# main.net
KiCad netlist of a schematic drawn in Altium Designer
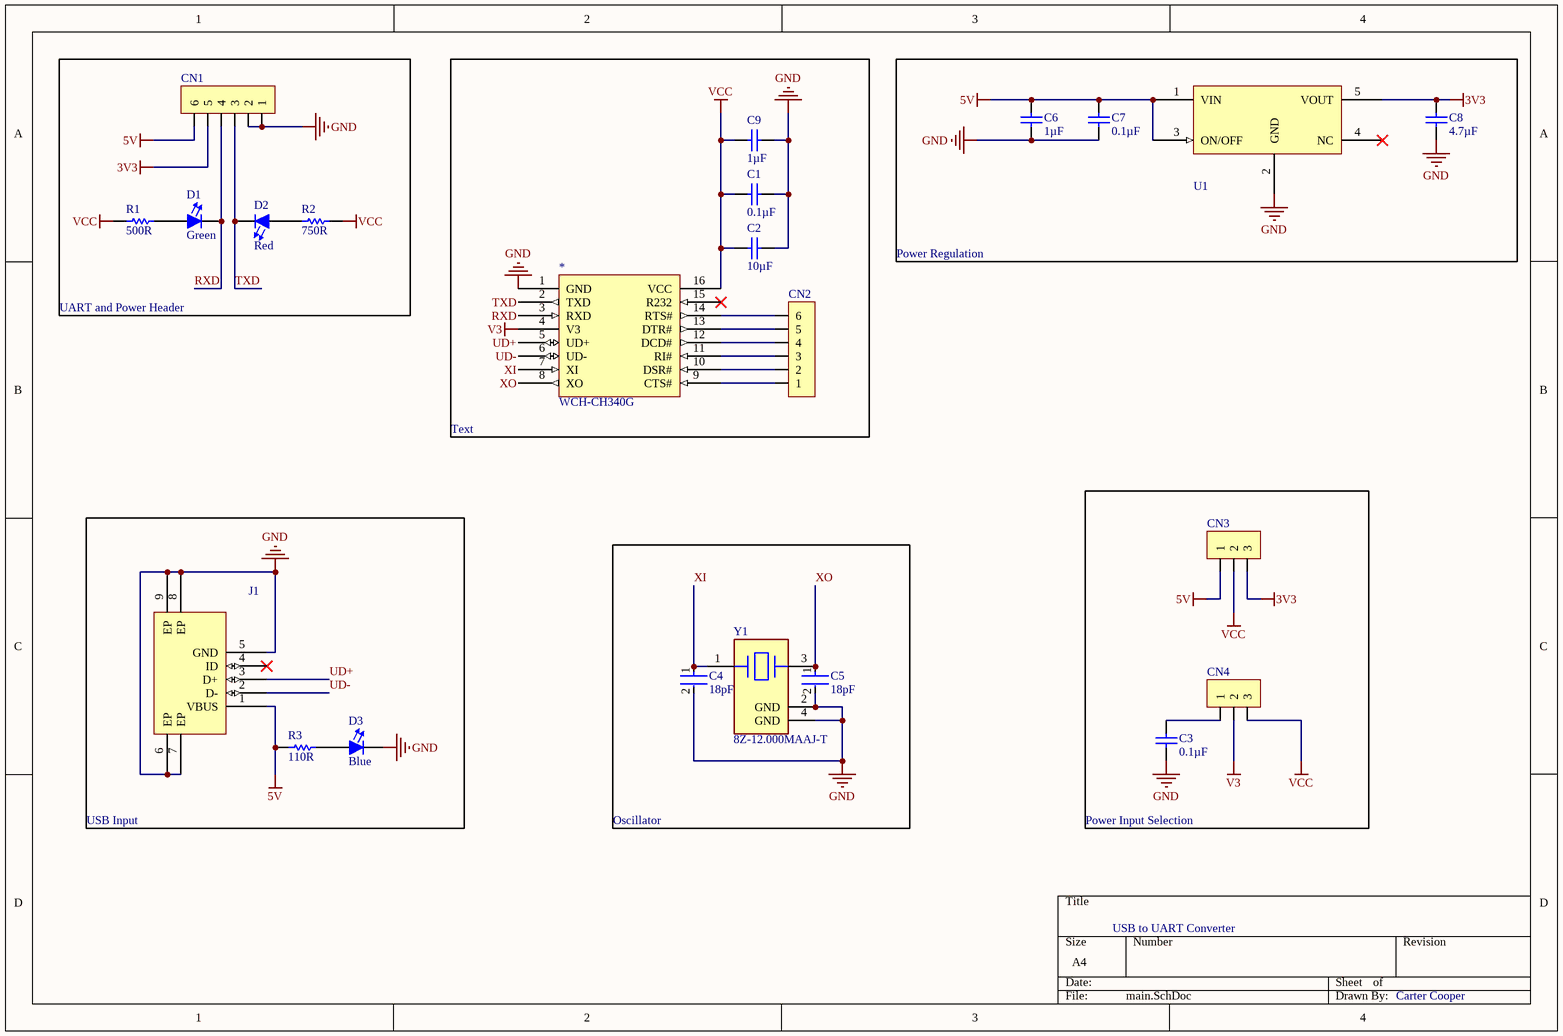
[diagram p0: main.SchDoc]

(export (version "E")
  (design (tool "Eeschema 10.0.6"))
  (components
    (comp (ref "*")
      (value "WCH-CH340G")
      (footprint "SOP127P600X175-16N")
      (description "USB to UART Transceiver. USB 2.0 2Mbps. LCSC #C14267")
      (fields (field (name "LCSC PART NUMBER") "C14267"))
      (libsource (lib "AUVIC") (part "WCH-CH340G"))
    )
    (comp (ref "C1")
      (value "0.1µF")
      (footprint "CAPC1608N(0603\")")
      (description "Capacitor, Ceramic, 16V, +/- 10%, 0603 SMD, X7R")
      (fields
        (field (name "Comment") "0.1uF 16V 0603 SMD, Ceramic")
        (field (name "CREATED BY") "Andy Bates")
        (field (name "SOURCE") "AUVic_Schematic_Library_Capacitors.SchLib")
        (field (name "PUBLISHER") "AUVic")
      )
      (libsource (lib "AUVIC") (part "Symbol"))
    )
    (comp (ref "C2")
      (value "10µF")
      (footprint "CAPC1608N(0603\")")
      (description "Capacitor, Ceramic, 16V, +/- 10%, 0603 SMD, X7R")
      (fields
        (field (name "Comment") "0.1uF 16V 0603 SMD, Ceramic")
        (field (name "CREATED BY") "Andy Bates")
        (field (name "SOURCE") "AUVic_Schematic_Library_Capacitors.SchLib")
        (field (name "PUBLISHER") "AUVic")
      )
      (libsource (lib "AUVIC") (part "Symbol"))
    )
    (comp (ref "C3")
      (value "0.1µF")
      (footprint "CAPC1608N(0603\")")
      (description "Capacitor, Ceramic, 16V, +/- 10%, 0603 SMD, X7R")
      (fields
        (field (name "Comment") "0.1uF 16V 0603 SMD, Ceramic")
        (field (name "CREATED BY") "Andy Bates")
        (field (name "SOURCE") "AUVic_Schematic_Library_Capacitors.SchLib")
        (field (name "PUBLISHER") "AUVic")
      )
      (libsource (lib "AUVIC") (part "Symbol"))
    )
    (comp (ref "C4")
      (value "CGA3E2C0G1H180J080AA")
      (footprint "FP-CGA3E-0_3-0_1-MFG")
      (description "CAP CER 18PF 50V C0G 0603")
      (fields (field (name "CAPACITANCE") "18pF") (field (name "TOLERANCE") "5%"))
      (libsource (lib "AUVIC") (part "b4654b650e69147ec39a6b967a45e02"))
    )
    (comp (ref "C5")
      (value "CGA3E2C0G1H180J080AA")
      (footprint "FP-CGA3E-0_3-0_1-MFG")
      (description "CAP CER 18PF 50V C0G 0603")
      (fields (field (name "CAPACITANCE") "18pF") (field (name "TOLERANCE") "5%"))
      (libsource (lib "AUVIC") (part "b4654b650e69147ec39a6b967a45e02"))
    )
    (comp (ref "C6")
      (value "1µF")
      (footprint "CAPC1608N(0603\")")
      (description "Capacitor, Ceramic, 50V, +/- 10%, 0603 SMD, X5R")
      (fields
        (field (name "Comment") "1uF 50V 0603 SMD, Ceramic")
        (field (name "CREATED BY") "Lyden Smith")
        (field (name "SOURCE") "AUVic_Schematic_Library_Capacitors.SchLib")
      )
      (libsource (lib "AUVIC") (part "Symbol"))
    )
    (comp (ref "C7")
      (value "0.1µF")
      (footprint "CAPC1608N(0603\")")
      (description "Capacitor, Ceramic, 16V, +/- 10%, 0603 SMD, X7R")
      (fields
        (field (name "Comment") "0.1uF 16V 0603 SMD, Ceramic")
        (field (name "CREATED BY") "Andy Bates")
        (field (name "SOURCE") "AUVic_Schematic_Library_Capacitors.SchLib")
        (field (name "PUBLISHER") "AUVic")
      )
      (libsource (lib "AUVIC") (part "Symbol"))
    )
    (comp (ref "C8")
      (value "4.7µF")
      (footprint "CAPC1608N(0603\")")
      (description "Capacitor, Ceramic, 10V, +/- 10%, 0603 SMD, X5R")
      (fields
        (field (name "MFG") "Samsung")
        (field (name "Comment") "4.7uF 10V 0603 SMD, Ceramic")
        (field (name "SOURCE") "AUVic_Schematic_Library_Capacitors.SchLib")
        (field (name "CREATED BY") "Ashwin Sira")
        (field (name "PUBLISHER") "AUVic")
      )
      (libsource (lib "AUVIC") (part "Symbol"))
    )
    (comp (ref "C9")
      (value "1µF")
      (footprint "CAPC1608N(0603\")")
      (description "Capacitor, Ceramic, 50V, +/- 10%, 0603 SMD, X5R")
      (fields
        (field (name "Comment") "1uF 50V 0603 SMD, Ceramic")
        (field (name "CREATED BY") "Lyden Smith")
        (field (name "SOURCE") "AUVic_Schematic_Library_Capacitors.SchLib")
      )
      (libsource (lib "AUVIC") (part "Symbol"))
    )
    (comp (ref "CN1")
      (value "Header, Male, 1x6")
      (footprint "Header, Male, 1X6")
      (description "1x6, Pads Pitch: 0.1\" (2.54mm), Through hole")
      (fields (field (name "SOURCE") "AUVic_Schematic_Library_Connectors.SchLib"))
      (libsource (lib "") (part "Symbol_4"))
    )
    (comp (ref "CN2")
      (value "Header, Male, 1x6")
      (footprint "Header, Male, 1X6")
      (description "1x6, Pads Pitch: 0.1\" (2.54mm), Through hole")
      (fields (field (name "SOURCE") "AUVic_Schematic_Library_Connectors.SchLib"))
      (libsource (lib "") (part "Symbol_1"))
    )
    (comp (ref "CN3")
      (value "Header, Male, 1x3, Pitch: 0.1\" (2.54mm), THT")
      (footprint "Header, Male, 1x3, Pitch: 0.1\" (2.54mm),THT")
      (fields
        (field (name "CREATED BY") "Ashwin Sira")
        (field (name "REVIEWED BY") "*")
        (field (name "SOURCE") "AUVic_Schematic_Library_Connectors.SchLib")
        (field (name "PUBLISHER") "AUVic")
      )
      (libsource (lib "") (part "Symbol_3"))
    )
    (comp (ref "CN4")
      (value "Header, Male, 1x3, Pitch: 0.1\" (2.54mm), THT")
      (footprint "Header, Male, 1x3, Pitch: 0.1\" (2.54mm),THT")
      (fields
        (field (name "CREATED BY") "Ashwin Sira")
        (field (name "REVIEWED BY") "*")
        (field (name "SOURCE") "AUVic_Schematic_Library_Connectors.SchLib")
        (field (name "PUBLISHER") "AUVic")
      )
      (libsource (lib "") (part "Symbol_3"))
    )
    (comp (ref "D1")
      (value "LT Q39G-Q1OO-25-1")
      (footprint "FP-LB_Q39E-MFG")
      (description "LED GREEN DIFFUSED 0603 SMD")
      (fields (field (name "COLOR") "Green"))
      (libsource (lib "") (part "Symbol_2"))
    )
    (comp (ref "D2")
      (value "LSQ976-NR-1")
      (footprint "FP-LB_Q39E-MFG")
      (description "LED Red 645nm 2-Pin Chip 0603(1608Metric) T/R")
      (fields (field (name "COLOR") "Red"))
      (libsource (lib "") (part "Symbol_2"))
    )
    (comp (ref "D3")
      (value "LBQ39E-N1OO-35-1")
      (footprint "FP-LB_Q39E-MFG")
      (description "LED BLUE DIFFUSED 0603 SMD")
      (fields (field (name "COLOR") "Blue"))
      (libsource (lib "") (part "Symbol_2"))
    )
    (comp (ref "J1")
      (value "USB - Micro B Female SMD")
      (footprint "Edge Connector")
      (description "USB - Micro B Female USB 2 5 SMD USB Connectors")
      (fields (field (name "LCSC PART NUMBER") "C319170") (field (name "CREATED BY") "Miguel Manguerra"))
      (libsource (lib "AUVIC") (part "USB - Micro B Female SMD"))
    )
    (comp (ref "R1")
      (value "RC0603FR-07750RL")
      (footprint "RESC0603(1608)_N")
      (description "Res Thick Film 0603 750 Ohm 1% 0.1W(1/10W) ±100ppm/C Epoxy SMD T/R")
      (fields (field (name "TOLERANCE") "1%") (field (name "RESISTANCE") "500R"))
      (libsource (lib "AUVIC") (part "RES"))
    )
    (comp (ref "R2")
      (value "RC0603FR-07750RL")
      (footprint "RESC0603(1608)_N")
      (description "Res Thick Film 0603 750 Ohm 1% 0.1W(1/10W) ±100ppm/C Epoxy SMD T/R")
      (fields (field (name "TOLERANCE") "1%") (field (name "RESISTANCE") "750R"))
      (libsource (lib "AUVIC") (part "RES"))
    )
    (comp (ref "R3")
      (value "RC0603FR-07110RL")
      (footprint "RESC1608X55X25ML10T15")
      (description "RES SMD 110 OHM 1% 1/10W 0603")
      (fields (field (name "TOLERANCE") "1%") (field (name "RESISTANCE") "110R"))
      (libsource (lib "AUVIC") (part "RES"))
    )
    (comp (ref "U1")
      (value "LP2981-33DBVR")
      (footprint "SOT95P280X145-5N")
      (description "IC REG LINEAR 3.3V 100MA SOT23-5")
      (libsource (lib "AUVIC") (part "LP2981-33DBVR"))
    )
    (comp (ref "Y1")
      (value "8Z-12.000MAAJ-T")
      (footprint "FP-8Z-MFG")
      (description "CRYSTAL 12.0000MHZ 18PF SMD")
      (fields (field (name "TOLERANCE") "30ppm"))
      (libsource (lib "Altium Content Vault") (part "82e0a36ce47690002882b131d1ef993"))
    )
  )
  (nets
    (net (code "1") (name "/RXD") (class "Default")
      (node (ref "*") (pin "3") (pinfunction "RXD_3") (pintype "input"))
      (node (ref "CN1") (pin "4") (pinfunction "4_4") (pintype "passive"))
      (node (ref "D1") (pin "1") (pinfunction "Cathode_1") (pintype "passive"))
    )
    (net (code "2") (name "/TXD") (class "Default")
      (node (ref "*") (pin "2") (pinfunction "TXD_2") (pintype "output"))
      (node (ref "CN1") (pin "3") (pinfunction "3_3") (pintype "passive"))
      (node (ref "D2") (pin "1") (pinfunction "Cathode_1") (pintype "passive"))
    )
    (net (code "3") (name "/UD+") (class "Default")
      (node (ref "*") (pin "5") (pinfunction "UD+_5") (pintype "bidirectional"))
      (node (ref "J1") (pin "3") (pinfunction "D+_3") (pintype "bidirectional"))
    )
    (net (code "4") (name "/UD-") (class "Default")
      (node (ref "*") (pin "6") (pinfunction "UD-_6") (pintype "bidirectional"))
      (node (ref "J1") (pin "2") (pinfunction "D-_2") (pintype "bidirectional"))
    )
    (net (code "5") (name "/XI") (class "Default")
      (node (ref "*") (pin "7") (pinfunction "XI_7") (pintype "input"))
      (node (ref "C4") (pin "1") (pinfunction "1_1") (pintype "passive"))
      (node (ref "Y1") (pin "1") (pinfunction "1_1") (pintype "passive"))
    )
    (net (code "6") (name "/XO") (class "Default")
      (node (ref "*") (pin "8") (pinfunction "XO_8") (pintype "output"))
      (node (ref "C5") (pin "1") (pinfunction "1_1") (pintype "passive"))
      (node (ref "Y1") (pin "3") (pinfunction "3_3") (pintype "passive"))
    )
    (net (code "7") (name "3V3") (class "Default")
      (node (ref "C8") (pin "2") (pinfunction "Cathode_2") (pintype "passive"))
      (node (ref "CN1") (pin "5") (pinfunction "5_5") (pintype "passive"))
      (node (ref "CN3") (pin "3") (pinfunction "3_3") (pintype "passive"))
      (node (ref "U1") (pin "5") (pinfunction "VOUT_5") (pintype "power_in"))
    )
    (net (code "8") (name "5V") (class "Default")
      (node (ref "C6") (pin "2") (pinfunction "Cathode_2") (pintype "passive"))
      (node (ref "C7") (pin "2") (pinfunction "Cathode_2") (pintype "passive"))
      (node (ref "CN1") (pin "6") (pinfunction "6_6") (pintype "passive"))
      (node (ref "CN3") (pin "1") (pinfunction "1_1") (pintype "passive"))
      (node (ref "J1") (pin "1") (pinfunction "VBUS_1") (pintype "power_in"))
      (node (ref "R3") (pin "2") (pinfunction "2_2") (pintype "passive"))
      (node (ref "U1") (pin "1") (pinfunction "VIN_1") (pintype "power_in"))
      (node (ref "U1") (pin "3") (pinfunction "ON/OFF_3") (pintype "input"))
    )
    (net (code "9") (name "GND") (class "Default")
      (node (ref "*") (pin "1") (pinfunction "GND_1") (pintype "power_in"))
      (node (ref "C1") (pin "2") (pinfunction "Cathode_2") (pintype "passive"))
      (node (ref "C2") (pin "2") (pinfunction "Cathode_2") (pintype "passive"))
      (node (ref "C3") (pin "1") (pinfunction "Anode_1") (pintype "passive"))
      (node (ref "C4") (pin "2") (pinfunction "2_2") (pintype "passive"))
      (node (ref "C5") (pin "2") (pinfunction "2_2") (pintype "passive"))
      (node (ref "C6") (pin "1") (pinfunction "Anode_1") (pintype "passive"))
      (node (ref "C7") (pin "1") (pinfunction "Anode_1") (pintype "passive"))
      (node (ref "C8") (pin "1") (pinfunction "Anode_1") (pintype "passive"))
      (node (ref "C9") (pin "2") (pinfunction "Cathode_2") (pintype "passive"))
      (node (ref "CN1") (pin "1") (pinfunction "1_1") (pintype "passive"))
      (node (ref "CN1") (pin "2") (pinfunction "2_2") (pintype "passive"))
      (node (ref "D3") (pin "1") (pinfunction "Cathode_1") (pintype "passive"))
      (node (ref "J1") (pin "5") (pinfunction "GND_5") (pintype "power_in"))
      (node (ref "J1") (pin "6") (pinfunction "EP_6") (pintype "passive"))
      (node (ref "J1") (pin "7") (pinfunction "EP_7") (pintype "passive"))
      (node (ref "J1") (pin "8") (pinfunction "EP_8") (pintype "passive"))
      (node (ref "J1") (pin "9") (pinfunction "EP_9") (pintype "passive"))
      (node (ref "U1") (pin "2") (pinfunction "GND_2") (pintype "power_in"))
      (node (ref "Y1") (pin "2") (pinfunction "GND_2") (pintype "power_in"))
      (node (ref "Y1") (pin "4") (pinfunction "GND_4") (pintype "power_in"))
    )
    (net (code "10") (name "Net-(*-CTS#)") (class "Default")
      (node (ref "*") (pin "9") (pinfunction "CTS#_9") (pintype "input"))
      (node (ref "CN2") (pin "1") (pinfunction "1_1") (pintype "passive"))
    )
    (net (code "11") (name "Net-(*-DCD#)") (class "Default")
      (node (ref "*") (pin "12") (pinfunction "DCD#_12") (pintype "output"))
      (node (ref "CN2") (pin "4") (pinfunction "4_4") (pintype "passive"))
    )
    (net (code "12") (name "Net-(*-DSR#)") (class "Default")
      (node (ref "*") (pin "10") (pinfunction "DSR#_10") (pintype "input"))
      (node (ref "CN2") (pin "2") (pinfunction "2_2") (pintype "passive"))
    )
    (net (code "13") (name "Net-(*-DTR#)") (class "Default")
      (node (ref "*") (pin "13") (pinfunction "DTR#_13") (pintype "output"))
      (node (ref "CN2") (pin "5") (pinfunction "5_5") (pintype "passive"))
    )
    (net (code "14") (name "Net-(*-RI#)") (class "Default")
      (node (ref "*") (pin "11") (pinfunction "RI#_11") (pintype "input"))
      (node (ref "CN2") (pin "3") (pinfunction "3_3") (pintype "passive"))
    )
    (net (code "15") (name "Net-(*-RTS#)") (class "Default")
      (node (ref "*") (pin "14") (pinfunction "RTS#_14") (pintype "output"))
      (node (ref "CN2") (pin "6") (pinfunction "6_6") (pintype "passive"))
    )
    (net (code "16") (name "Net-(C3-Cathode)") (class "Default")
      (node (ref "C3") (pin "2") (pinfunction "Cathode_2") (pintype "passive"))
      (node (ref "CN4") (pin "1") (pinfunction "1_1") (pintype "passive"))
    )
    (net (code "17") (name "Net-(D1-Anode)") (class "Default")
      (node (ref "D1") (pin "2") (pinfunction "Anode_2") (pintype "passive"))
      (node (ref "R1") (pin "2") (pinfunction "2_2") (pintype "passive"))
    )
    (net (code "18") (name "Net-(D2-Anode)") (class "Default")
      (node (ref "D2") (pin "2") (pinfunction "Anode_2") (pintype "passive"))
      (node (ref "R2") (pin "1") (pinfunction "1_1") (pintype "passive"))
    )
    (net (code "19") (name "Net-(D3-Anode)") (class "Default")
      (node (ref "D3") (pin "2") (pinfunction "Anode_2") (pintype "passive"))
      (node (ref "R3") (pin "1") (pinfunction "1_1") (pintype "passive"))
    )
    (net (code "20") (name "V3") (class "Default")
      (node (ref "*") (pin "4") (pinfunction "V3_4") (pintype "power_in"))
      (node (ref "CN4") (pin "2") (pinfunction "2_2") (pintype "passive"))
    )
    (net (code "21") (name "VCC") (class "Default")
      (node (ref "*") (pin "16") (pinfunction "VCC_16") (pintype "power_in"))
      (node (ref "C1") (pin "1") (pinfunction "Anode_1") (pintype "passive"))
      (node (ref "C2") (pin "1") (pinfunction "Anode_1") (pintype "passive"))
      (node (ref "C9") (pin "1") (pinfunction "Anode_1") (pintype "passive"))
      (node (ref "CN3") (pin "2") (pinfunction "2_2") (pintype "passive"))
      (node (ref "CN4") (pin "3") (pinfunction "3_3") (pintype "passive"))
      (node (ref "R1") (pin "1") (pinfunction "1_1") (pintype "passive"))
      (node (ref "R2") (pin "2") (pinfunction "2_2") (pintype "passive"))
    )
    (net (code "22") (name "unconnected-(*-R232-Pad15)") (class "Default")
      (node (ref "*") (pin "15") (pinfunction "R232_15") (pintype "input+no_connect"))
    )
    (net (code "23") (name "unconnected-(J1-ID-Pad4)") (class "Default")
      (node (ref "J1") (pin "4") (pinfunction "ID_4") (pintype "bidirectional+no_connect"))
    )
    (net (code "24") (name "unconnected-(U1-NC-Pad4)") (class "Default")
      (node (ref "U1") (pin "4") (pinfunction "NC_4") (pintype "passive+no_connect"))
    )
  )
)
